# pj7.net
KiCad netlist of a schematic drawn in EAGLE
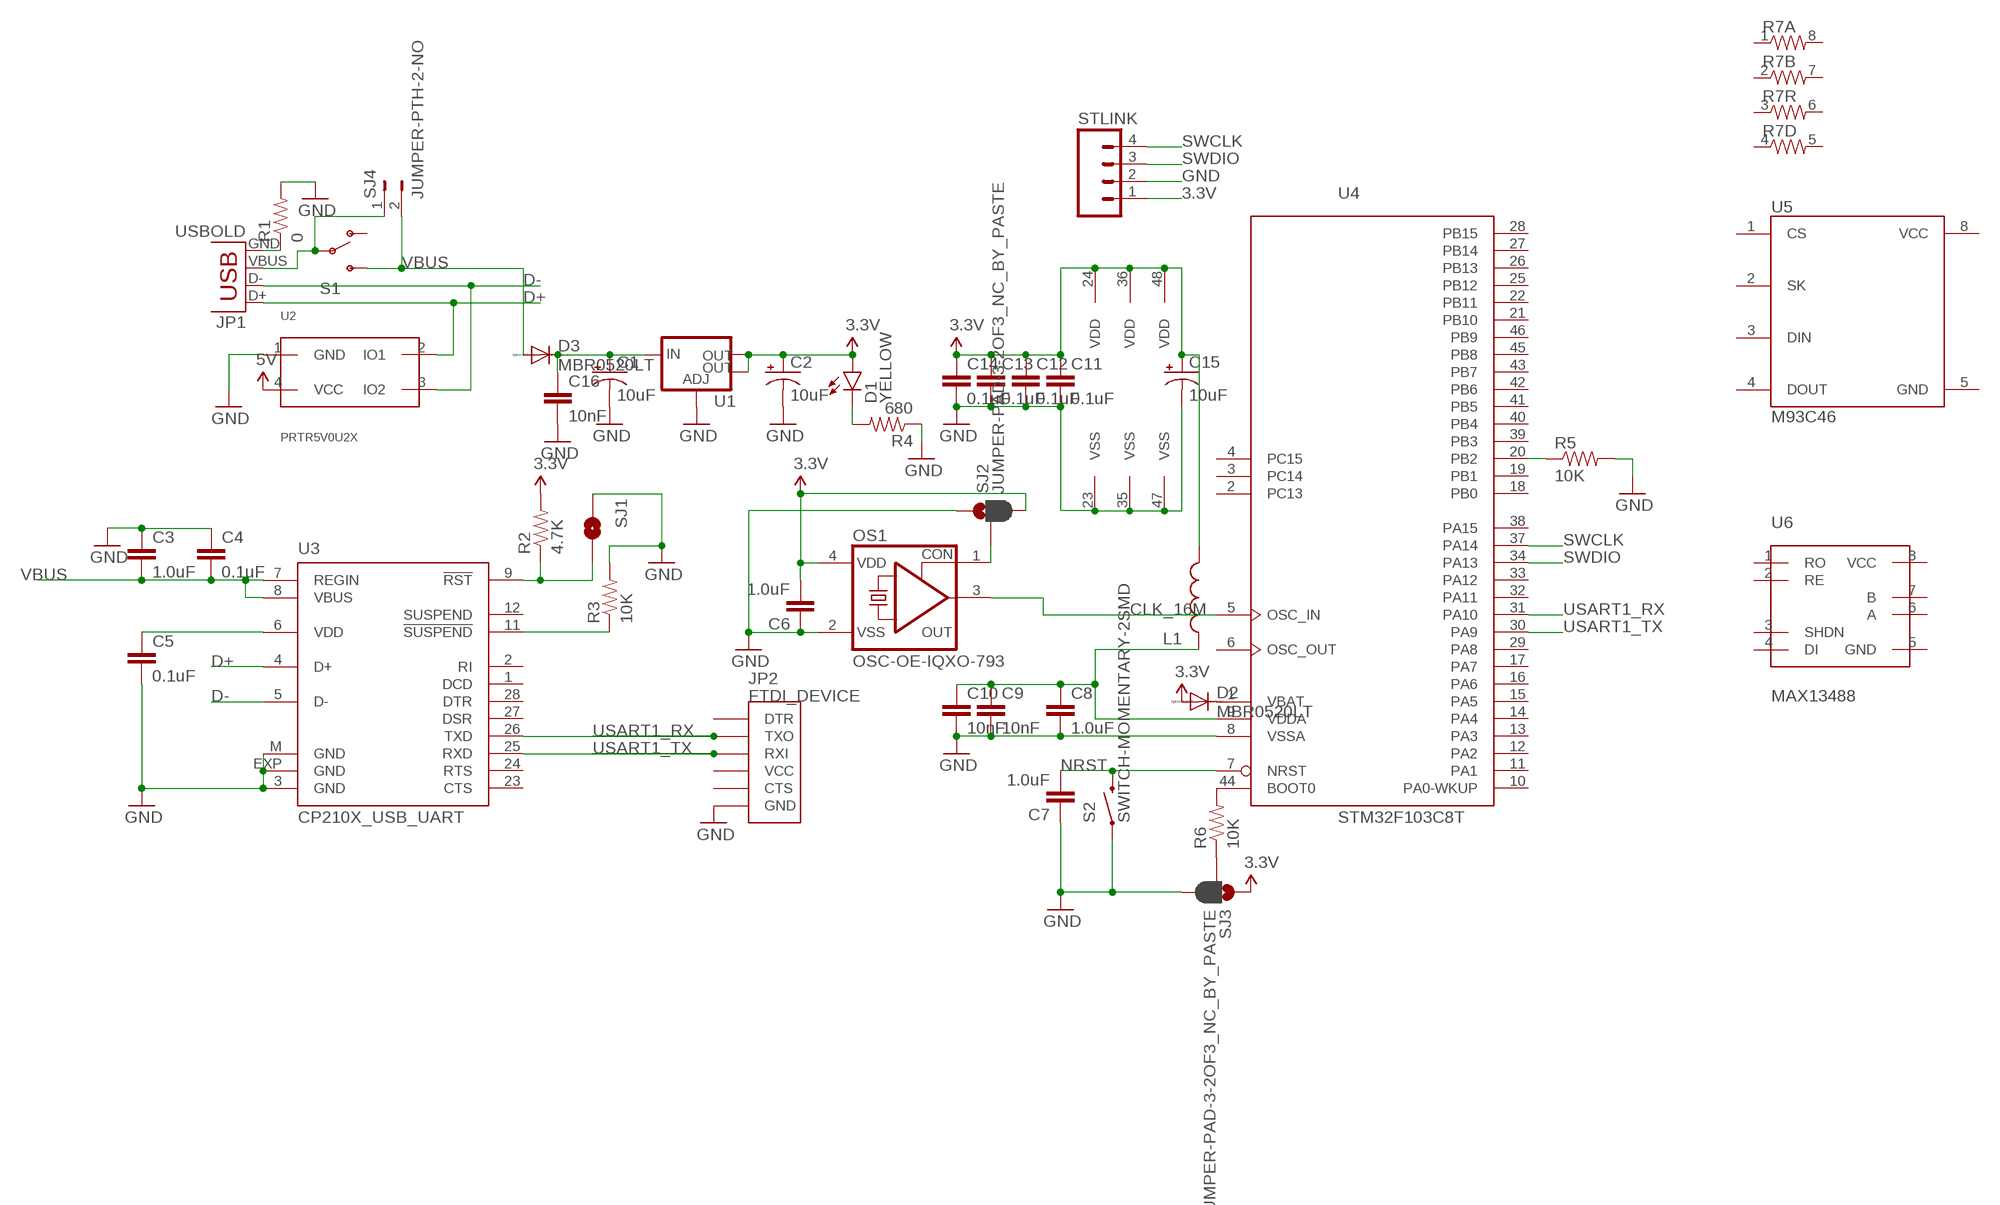
[diagram p0: schematic, sheet 1]

(export (version "E")
  (design (tool "Eeschema 10.0.6"))
  (components
    (comp (ref "C1")
      (value "10uF")
      (footprint "eagle-import:EIA3216")
      (libsource (lib "eagle-import") (part "10UF-16V-10%(TANT)"))
    )
    (comp (ref "C2")
      (value "10uF")
      (footprint "eagle-import:EIA3216")
      (libsource (lib "eagle-import") (part "10UF-16V-10%(TANT)"))
    )
    (comp (ref "C3")
      (value "1.0uF")
      (footprint "eagle-import:0603-CAP")
      (libsource (lib "eagle-import") (part "1.0UF-16V-10%(0603)"))
    )
    (comp (ref "C4")
      (value "0.1uF")
      (footprint "eagle-import:0603-CAP")
      (libsource (lib "eagle-import") (part "0.1UF-25V-5%(0603)"))
    )
    (comp (ref "C5")
      (value "0.1uF")
      (footprint "eagle-import:0603-CAP")
      (libsource (lib "eagle-import") (part "0.1UF-25V-5%(0603)"))
    )
    (comp (ref "C6")
      (value "1.0uF")
      (footprint "eagle-import:0603-CAP")
      (libsource (lib "eagle-import") (part "1.0UF-16V-10%(0603)"))
    )
    (comp (ref "C7")
      (value "1.0uF")
      (footprint "eagle-import:0603-CAP")
      (libsource (lib "eagle-import") (part "1.0UF-16V-10%(0603)"))
    )
    (comp (ref "C8")
      (value "1.0uF")
      (footprint "eagle-import:0603-CAP")
      (libsource (lib "eagle-import") (part "1.0UF-16V-10%(0603)"))
    )
    (comp (ref "C9")
      (value "10nF")
      (footprint "eagle-import:0603-CAP")
      (libsource (lib "eagle-import") (part "10NF/10000PF-50V-10%(0603)"))
    )
    (comp (ref "C10")
      (value "10nF")
      (footprint "eagle-import:0603-CAP")
      (libsource (lib "eagle-import") (part "10NF/10000PF-50V-10%(0603)"))
    )
    (comp (ref "C11")
      (value "0.1uF")
      (footprint "eagle-import:0603-CAP")
      (libsource (lib "eagle-import") (part "0.1UF-25V-5%(0603)"))
    )
    (comp (ref "C12")
      (value "0.1uF")
      (footprint "eagle-import:0603-CAP")
      (libsource (lib "eagle-import") (part "0.1UF-25V-5%(0603)"))
    )
    (comp (ref "C13")
      (value "0.1uF")
      (footprint "eagle-import:0603-CAP")
      (libsource (lib "eagle-import") (part "0.1UF-25V-5%(0603)"))
    )
    (comp (ref "C14")
      (value "0.1uF")
      (footprint "eagle-import:0603-CAP")
      (libsource (lib "eagle-import") (part "0.1UF-25V-5%(0603)"))
    )
    (comp (ref "C15")
      (value "10uF")
      (footprint "eagle-import:EIA3216")
      (libsource (lib "eagle-import") (part "10UF-16V-10%(TANT)"))
    )
    (comp (ref "C16")
      (value "10nF")
      (footprint "eagle-import:0603-CAP")
      (libsource (lib "eagle-import") (part "10NF/10000PF-50V-10%(0603)"))
    )
    (comp (ref "D1")
      (value "YELLOW")
      (footprint "eagle-import:LED-1206")
      (libsource (lib "eagle-import") (part "LED-YELLOW1206"))
    )
    (comp (ref "D2")
      (value "MBR0520LT")
      (footprint "eagle-import:SOD123")
      (libsource (lib "eagle-import") (part "MBR0520LT"))
    )
    (comp (ref "D3")
      (value "MBR0520LT")
      (footprint "eagle-import:SOD123")
      (libsource (lib "eagle-import") (part "MBR0520LT"))
    )
    (comp (ref "JP1")
      (value "USBOLD")
      (footprint "eagle-import:USB-MINIB-OLD")
      (libsource (lib "eagle-import") (part "USBOLD"))
    )
    (comp (ref "JP2")
      (value "FTDI_DEVICE")
      (footprint "eagle-import:FTDI_DEVICE_SIDE")
      (libsource (lib "eagle-import") (part "FTDI_DEVICE"))
    )
    (comp (ref "L1")
      (value "INDUCTOR0603")
      (footprint "eagle-import:0603")
      (libsource (lib "eagle-import") (part "INDUCTOR0603"))
    )
    (comp (ref "OS1")
      (value "OSC-OE-IQXO-793")
      (footprint "eagle-import:2.5X2-4-PAD")
      (libsource (lib "eagle-import") (part "OSC-OE-IQXO-793"))
    )
    (comp (ref "R1")
      (value "0")
      (footprint "eagle-import:0603")
      (libsource (lib "eagle-import") (part "0OHM-1/10W-5%(0603)"))
    )
    (comp (ref "R2")
      (value "4.7K")
      (footprint "eagle-import:0603-RES")
      (libsource (lib "eagle-import") (part "4.7KOHM-1/10W-1%(0603)"))
    )
    (comp (ref "R3")
      (value "10K")
      (footprint "eagle-import:0603-RES")
      (libsource (lib "eagle-import") (part "4.7KOHM-1/10W-1%(0603)"))
    )
    (comp (ref "R4")
      (value "680")
      (footprint "eagle-import:0603-RES")
      (libsource (lib "eagle-import") (part "680OHM1/10W5%(0603)"))
    )
    (comp (ref "R5")
      (value "10K")
      (footprint "eagle-import:0603-RES")
      (libsource (lib "eagle-import") (part "10KOHM-1/10W-1%(0603)0603"))
    )
    (comp (ref "R6")
      (value "10K")
      (footprint "eagle-import:0603-RES")
      (libsource (lib "eagle-import") (part "10KOHM-1/10W-1%(0603)0603"))
    )
    (comp (ref "R7")
      (value "RESISTOR-ARRAY0603-ARV")
      (footprint "eagle-import:0603-ARV")
      (libsource (lib "eagle-import") (part "RESISTOR-ARRAY0603-ARV"))
    )
    (comp (ref "S1")
      (value "SWITCH-SPDTSMD")
      (footprint "eagle-import:AYZ0202")
      (libsource (lib "eagle-import") (part "SWITCH-SPDTSMD"))
    )
    (comp (ref "S2")
      (value "SWITCH-MOMENTARY-2SMD")
      (footprint "eagle-import:TACTILE-SWITCH-SMD")
      (libsource (lib "eagle-import") (part "SWITCH-MOMENTARY-2SMD"))
    )
    (comp (ref "SJ1")
      (value "JUMPER-PAD-2-NOYES_SILK")
      (footprint "eagle-import:PAD-JUMPER-2-NO_YES_SILK")
      (libsource (lib "eagle-import") (part "JUMPER-PAD-2-NOYES_SILK"))
    )
    (comp (ref "SJ2")
      (value "JUMPER-PAD-3-2OF3_NC_BY_PASTE")
      (footprint "eagle-import:PAD-JUMPER-3-2OF3_NC_BY_PASTE_YES_SILK_FULL_BOX")
      (libsource (lib "eagle-import") (part "JUMPER-PAD-3-2OF3_NC_BY_PASTE"))
    )
    (comp (ref "SJ3")
      (value "JUMPER-PAD-3-2OF3_NC_BY_PASTE")
      (footprint "eagle-import:PAD-JUMPER-3-2OF3_NC_BY_PASTE_YES_SILK_FULL_BOX")
      (libsource (lib "eagle-import") (part "JUMPER-PAD-3-2OF3_NC_BY_PASTE"))
    )
    (comp (ref "SJ4")
      (value "JUMPER-PTH-2-NO")
      (footprint "eagle-import:PTH-JUMPER-2-NO_NO_SILK")
      (libsource (lib "eagle-import") (part "JUMPER-PTH-2-NO"))
    )
    (comp (ref "STLINK")
      (value "M04LOCK")
      (footprint "eagle-import:1X04_LOCK")
      (libsource (lib "eagle-import") (part "M04LOCK"))
    )
    (comp (ref "U1")
      (value "V_REG_LM1117SOT223")
      (footprint "eagle-import:SOT223")
      (libsource (lib "eagle-import") (part "V_REG_LM1117SOT223"))
    )
    (comp (ref "U2")
      (value "PRTR5V0U2X")
      (footprint "eagle-import:SOT143")
      (libsource (lib "eagle-import") (part "PRTR5V0U2X"))
    )
    (comp (ref "U3")
      (value "CP210X_USB_UART")
      (footprint "eagle-import:MLP28")
      (libsource (lib "eagle-import") (part "CP210X_USB_UART"))
    )
    (comp (ref "U4")
      (value "STM32F103C8T")
      (footprint "eagle-import:LQFP48")
      (libsource (lib "eagle-import") (part "STM32F103CT8"))
    )
    (comp (ref "U5")
      (value "M93C46")
      (footprint "eagle-import:SO08")
      (libsource (lib "eagle-import") (part "M93C46"))
    )
    (comp (ref "U6")
      (value "MAX13488")
      (footprint "eagle-import:SOIC8")
      (libsource (lib "eagle-import") (part "MAX13488"))
    )
  )
  (nets
    (net (code "1") (name "/CLK_16M") (class "Default")
      (node (ref "OS1") (pin "3") (pinfunction "OUT_3") (pintype "output"))
      (node (ref "U4") (pin "5") (pinfunction "OSC_IN_5") (pintype "bidirectional"))
    )
    (net (code "2") (name "/D+") (class "Default")
      (node (ref "JP1") (pin "D+") (pinfunction "D+_D+") (pintype "bidirectional"))
      (node (ref "U2") (pin "2") (pinfunction "IO1_2") (pintype "bidirectional"))
      (node (ref "U3") (pin "4") (pinfunction "D+_4") (pintype "bidirectional"))
    )
    (net (code "3") (name "/D-") (class "Default")
      (node (ref "JP1") (pin "D-") (pinfunction "D-_D-") (pintype "bidirectional"))
      (node (ref "U2") (pin "3") (pinfunction "IO2_3") (pintype "bidirectional"))
      (node (ref "U3") (pin "5") (pinfunction "D-_5") (pintype "bidirectional"))
    )
    (net (code "4") (name "/NRST") (class "Default")
      (node (ref "C7") (pin "2") (pinfunction "2_2") (pintype "passive"))
      (node (ref "S2") (pin "3") (pinfunction "2_3") (pintype "passive"))
      (node (ref "U4") (pin "7") (pinfunction "NRST_7") (pintype "bidirectional"))
    )
    (net (code "5") (name "/SWCLK") (class "Default")
      (node (ref "STLINK") (pin "4") (pinfunction "4_4") (pintype "passive"))
      (node (ref "U4") (pin "37") (pinfunction "PA14_37") (pintype "bidirectional"))
    )
    (net (code "6") (name "/SWDIO") (class "Default")
      (node (ref "STLINK") (pin "3") (pinfunction "3_3") (pintype "passive"))
      (node (ref "U4") (pin "34") (pinfunction "PA13_34") (pintype "bidirectional"))
    )
    (net (code "7") (name "/USART1_RX") (class "Default")
      (node (ref "JP2") (pin "P$2") (pinfunction "TXO_P$2") (pintype "bidirectional"))
      (node (ref "U3") (pin "26") (pinfunction "TXD_26") (pintype "output"))
      (node (ref "U4") (pin "31") (pinfunction "PA10_31") (pintype "bidirectional"))
    )
    (net (code "8") (name "/USART1_TX") (class "Default")
      (node (ref "JP2") (pin "P$3") (pinfunction "RXI_P$3") (pintype "bidirectional"))
      (node (ref "U3") (pin "25") (pinfunction "RXD_25") (pintype "input"))
      (node (ref "U4") (pin "30") (pinfunction "PA9_30") (pintype "bidirectional"))
    )
    (net (code "9") (name "/VBUS") (class "Default")
      (node (ref "C3") (pin "2") (pinfunction "2_2") (pintype "passive"))
      (node (ref "C4") (pin "2") (pinfunction "2_2") (pintype "passive"))
      (node (ref "D3") (pin "A") (pinfunction "A_A") (pintype "passive"))
      (node (ref "S1") (pin "3") (pinfunction "S_3") (pintype "passive"))
      (node (ref "SJ4") (pin "2") (pinfunction "2_2") (pintype "passive"))
      (node (ref "U3") (pin "7") (pinfunction "REGIN_7") (pintype "passive"))
      (node (ref "U3") (pin "8") (pinfunction "VBUS_8") (pintype "input"))
    )
    (net (code "10") (name "3.3V") (class "Default")
      (node (ref "C11") (pin "1") (pinfunction "1_1") (pintype "passive"))
      (node (ref "C12") (pin "1") (pinfunction "1_1") (pintype "passive"))
      (node (ref "C13") (pin "1") (pinfunction "1_1") (pintype "passive"))
      (node (ref "C14") (pin "1") (pinfunction "1_1") (pintype "passive"))
      (node (ref "C15") (pin "A") (pinfunction "+_A") (pintype "passive"))
      (node (ref "C2") (pin "A") (pinfunction "+_A") (pintype "passive"))
      (node (ref "C6") (pin "2") (pinfunction "2_2") (pintype "passive"))
      (node (ref "D1") (pin "A") (pinfunction "A_A") (pintype "passive"))
      (node (ref "D2") (pin "A") (pinfunction "A_A") (pintype "passive"))
      (node (ref "L1") (pin "2") (pinfunction "2_2") (pintype "passive"))
      (node (ref "OS1") (pin "4") (pinfunction "VDD_4") (pintype "power_in"))
      (node (ref "R2") (pin "2") (pinfunction "2_2") (pintype "passive"))
      (node (ref "SJ2") (pin "3") (pinfunction "3_3") (pintype "passive"))
      (node (ref "SJ3") (pin "1") (pinfunction "1_1") (pintype "passive"))
      (node (ref "STLINK") (pin "1") (pinfunction "1_1") (pintype "passive"))
      (node (ref "U1") (pin "2") (pinfunction "OUT_2") (pintype "output"))
      (node (ref "U1") (pin "4") (pinfunction "OUT_4") (pintype "output"))
      (node (ref "U4") (pin "24") (pinfunction "VDD_24") (pintype "power_in"))
      (node (ref "U4") (pin "36") (pinfunction "VDD_36") (pintype "power_in"))
      (node (ref "U4") (pin "48") (pinfunction "VDD_48") (pintype "power_in"))
    )
    (net (code "11") (name "5V") (class "Default")
      (node (ref "U2") (pin "4") (pinfunction "VCC_4") (pintype "bidirectional"))
    )
    (net (code "12") (name "GND") (class "Default")
      (node (ref "C1") (pin "C") (pinfunction "-_C") (pintype "passive"))
      (node (ref "C10") (pin "2") (pinfunction "2_2") (pintype "passive"))
      (node (ref "C11") (pin "2") (pinfunction "2_2") (pintype "passive"))
      (node (ref "C12") (pin "2") (pinfunction "2_2") (pintype "passive"))
      (node (ref "C13") (pin "2") (pinfunction "2_2") (pintype "passive"))
      (node (ref "C14") (pin "2") (pinfunction "2_2") (pintype "passive"))
      (node (ref "C15") (pin "C") (pinfunction "-_C") (pintype "passive"))
      (node (ref "C16") (pin "2") (pinfunction "2_2") (pintype "passive"))
      (node (ref "C2") (pin "C") (pinfunction "-_C") (pintype "passive"))
      (node (ref "C3") (pin "1") (pinfunction "1_1") (pintype "passive"))
      (node (ref "C4") (pin "1") (pinfunction "1_1") (pintype "passive"))
      (node (ref "C5") (pin "2") (pinfunction "2_2") (pintype "passive"))
      (node (ref "C6") (pin "1") (pinfunction "1_1") (pintype "passive"))
      (node (ref "C7") (pin "1") (pinfunction "1_1") (pintype "passive"))
      (node (ref "C8") (pin "2") (pinfunction "2_2") (pintype "passive"))
      (node (ref "C9") (pin "2") (pinfunction "2_2") (pintype "passive"))
      (node (ref "JP2") (pin "P$6") (pinfunction "GND_P$6") (pintype "bidirectional"))
      (node (ref "OS1") (pin "2") (pinfunction "VSS_2") (pintype "power_in"))
      (node (ref "R1") (pin "2") (pinfunction "2_2") (pintype "passive"))
      (node (ref "R3") (pin "2") (pinfunction "2_2") (pintype "passive"))
      (node (ref "R4") (pin "1") (pinfunction "1_1") (pintype "passive"))
      (node (ref "R5") (pin "2") (pinfunction "2_2") (pintype "passive"))
      (node (ref "S2") (pin "1") (pinfunction "1_1") (pintype "passive"))
      (node (ref "SJ1") (pin "2") (pinfunction "2_2") (pintype "passive"))
      (node (ref "SJ2") (pin "1") (pinfunction "1_1") (pintype "passive"))
      (node (ref "SJ3") (pin "3") (pinfunction "3_3") (pintype "passive"))
      (node (ref "STLINK") (pin "2") (pinfunction "2_2") (pintype "passive"))
      (node (ref "U1") (pin "1") (pinfunction "ADJ_1") (pintype "input"))
      (node (ref "U2") (pin "1") (pinfunction "GND_1") (pintype "bidirectional"))
      (node (ref "U3") (pin "3") (pinfunction "GND_3") (pintype "power_in"))
      (node (ref "U3") (pin "EXP") (pinfunction "GND_EXP") (pintype "power_in"))
      (node (ref "U3") (pin "M") (pinfunction "GND_M") (pintype "power_in"))
      (node (ref "U4") (pin "23") (pinfunction "VSS_23") (pintype "power_in"))
      (node (ref "U4") (pin "35") (pinfunction "VSS_35") (pintype "power_in"))
      (node (ref "U4") (pin "47") (pinfunction "VSS_47") (pintype "power_in"))
      (node (ref "U4") (pin "8") (pinfunction "VSSA_8") (pintype "power_in"))
    )
    (net (code "13") (name "Net-(C1-+)") (class "Default")
      (node (ref "C1") (pin "A") (pinfunction "+_A") (pintype "passive"))
      (node (ref "C16") (pin "1") (pinfunction "1_1") (pintype "passive"))
      (node (ref "D3") (pin "C") (pinfunction "C_C") (pintype "passive"))
      (node (ref "U1") (pin "3") (pinfunction "IN_3") (pintype "input"))
    )
    (net (code "14") (name "Net-(D1-PadC)") (class "Default")
      (node (ref "D1") (pin "C") (pinfunction "C_C") (pintype "passive"))
      (node (ref "R4") (pin "2") (pinfunction "2_2") (pintype "passive"))
    )
    (net (code "15") (name "Net-(JP1-PadGND)") (class "Default")
      (node (ref "JP1") (pin "GND") (pinfunction "GND_GND") (pintype "bidirectional"))
      (node (ref "R1") (pin "1") (pinfunction "1_1") (pintype "passive"))
    )
    (net (code "16") (name "Net-(OS1-CON)") (class "Default")
      (node (ref "OS1") (pin "1") (pinfunction "CON_1") (pintype "input"))
      (node (ref "SJ2") (pin "2") (pinfunction "2_2") (pintype "passive"))
    )
    (net (code "17") (name "Net-(R6-Pad1)") (class "Default")
      (node (ref "R6") (pin "1") (pinfunction "1_1") (pintype "passive"))
      (node (ref "SJ3") (pin "2") (pinfunction "2_2") (pintype "passive"))
    )
    (net (code "18") (name "Net-(S1-P)") (class "Default")
      (node (ref "JP1") (pin "VBUS") (pinfunction "VBUS_VBUS") (pintype "bidirectional"))
      (node (ref "S1") (pin "2") (pinfunction "P_2") (pintype "passive"))
      (node (ref "SJ4") (pin "1") (pinfunction "1_1") (pintype "passive"))
    )
    (net (code "19") (name "Net-(U3-VDD)") (class "Default")
      (node (ref "C5") (pin "1") (pinfunction "1_1") (pintype "passive"))
      (node (ref "U3") (pin "6") (pinfunction "VDD_6") (pintype "power_in"))
    )
    (net (code "20") (name "Net-(U3-~{RST})") (class "Default")
      (node (ref "R2") (pin "1") (pinfunction "1_1") (pintype "passive"))
      (node (ref "SJ1") (pin "1") (pinfunction "1_1") (pintype "passive"))
      (node (ref "U3") (pin "9") (pinfunction "~{RST}_9") (pintype "bidirectional"))
    )
    (net (code "21") (name "Net-(U3-~{SUSPEND})") (class "Default")
      (node (ref "R3") (pin "1") (pinfunction "1_1") (pintype "passive"))
      (node (ref "U3") (pin "11") (pinfunction "~{SUSPEND}_11") (pintype "output"))
    )
    (net (code "22") (name "Net-(U4A-BOOT0)") (class "Default")
      (node (ref "R6") (pin "2") (pinfunction "2_2") (pintype "passive"))
      (node (ref "U4") (pin "44") (pinfunction "BOOT0_44") (pintype "input"))
    )
    (net (code "23") (name "Net-(U4A-PB2)") (class "Default")
      (node (ref "R5") (pin "1") (pinfunction "1_1") (pintype "passive"))
      (node (ref "U4") (pin "20") (pinfunction "PB2_20") (pintype "bidirectional"))
    )
    (net (code "24") (name "Net-(U4A-VBAT)") (class "Default")
      (node (ref "D2") (pin "C") (pinfunction "C_C") (pintype "passive"))
      (node (ref "U4") (pin "1") (pinfunction "VBAT_1") (pintype "power_in"))
    )
    (net (code "25") (name "Net-(U4A-VDDA)") (class "Default")
      (node (ref "C10") (pin "1") (pinfunction "1_1") (pintype "passive"))
      (node (ref "C8") (pin "1") (pinfunction "1_1") (pintype "passive"))
      (node (ref "C9") (pin "1") (pinfunction "1_1") (pintype "passive"))
      (node (ref "L1") (pin "1") (pinfunction "1_1") (pintype "passive"))
      (node (ref "U4") (pin "9") (pinfunction "VDDA_9") (pintype "power_in"))
    )
    (net (code "26") (name "unconnected-(JP2-CTS-PadP$5)") (class "Default")
      (node (ref "JP2") (pin "P$5") (pinfunction "CTS_P$5") (pintype "bidirectional"))
    )
    (net (code "27") (name "unconnected-(JP2-DTR-PadP$1)") (class "Default")
      (node (ref "JP2") (pin "P$1") (pinfunction "DTR_P$1") (pintype "bidirectional"))
    )
    (net (code "28") (name "unconnected-(JP2-VCC-PadP$4)") (class "Default")
      (node (ref "JP2") (pin "P$4") (pinfunction "VCC_P$4") (pintype "bidirectional"))
    )
    (net (code "29") (name "unconnected-(R7-Pad1)") (class "Default")
      (node (ref "R7") (pin "1") (pinfunction "1_1") (pintype "passive"))
    )
    (net (code "30") (name "unconnected-(R7A-2-Pad8)") (class "Default")
      (node (ref "R7") (pin "8") (pinfunction "2_8") (pintype "passive"))
    )
    (net (code "31") (name "unconnected-(R7B-1-Pad2)") (class "Default")
      (node (ref "R7") (pin "2") (pinfunction "1_2") (pintype "passive"))
    )
    (net (code "32") (name "unconnected-(R7B-2-Pad7)") (class "Default")
      (node (ref "R7") (pin "7") (pinfunction "2_7") (pintype "passive"))
    )
    (net (code "33") (name "unconnected-(R7C-1-Pad4)") (class "Default")
      (node (ref "R7") (pin "4") (pinfunction "1_4") (pintype "passive"))
    )
    (net (code "34") (name "unconnected-(R7C-2-Pad5)") (class "Default")
      (node (ref "R7") (pin "5") (pinfunction "2_5") (pintype "passive"))
    )
    (net (code "35") (name "unconnected-(R7D-1-Pad3)") (class "Default")
      (node (ref "R7") (pin "3") (pinfunction "1_3") (pintype "passive"))
    )
    (net (code "36") (name "unconnected-(R7D-2-Pad6)") (class "Default")
      (node (ref "R7") (pin "6") (pinfunction "2_6") (pintype "passive"))
    )
    (net (code "37") (name "unconnected-(S1-O-Pad1)") (class "Default")
      (node (ref "S1") (pin "1") (pinfunction "O_1") (pintype "passive"))
    )
    (net (code "38") (name "unconnected-(U3-CTS-Pad23)") (class "Default")
      (node (ref "U3") (pin "23") (pinfunction "CTS_23") (pintype "input"))
    )
    (net (code "39") (name "unconnected-(U3-DCD-Pad1)") (class "Default")
      (node (ref "U3") (pin "1") (pinfunction "DCD_1") (pintype "input"))
    )
    (net (code "40") (name "unconnected-(U3-DSR-Pad27)") (class "Default")
      (node (ref "U3") (pin "27") (pinfunction "DSR_27") (pintype "input"))
    )
    (net (code "41") (name "unconnected-(U3-DTR-Pad28)") (class "Default")
      (node (ref "U3") (pin "28") (pinfunction "DTR_28") (pintype "output"))
    )
    (net (code "42") (name "unconnected-(U3-RI-Pad2)") (class "Default")
      (node (ref "U3") (pin "2") (pinfunction "RI_2") (pintype "input"))
    )
    (net (code "43") (name "unconnected-(U3-RTS-Pad24)") (class "Default")
      (node (ref "U3") (pin "24") (pinfunction "RTS_24") (pintype "output"))
    )
    (net (code "44") (name "unconnected-(U3-SUSPEND-Pad12)") (class "Default")
      (node (ref "U3") (pin "12") (pinfunction "SUSPEND_12") (pintype "output"))
    )
    (net (code "45") (name "unconnected-(U4A-OSC_OUT-Pad6)") (class "Default")
      (node (ref "U4") (pin "6") (pinfunction "OSC_OUT_6") (pintype "bidirectional"))
    )
    (net (code "46") (name "unconnected-(U4A-PA0-WKUP-Pad10)") (class "Default")
      (node (ref "U4") (pin "10") (pinfunction "PA0-WKUP_10") (pintype "bidirectional"))
    )
    (net (code "47") (name "unconnected-(U4A-PA1-Pad11)") (class "Default")
      (node (ref "U4") (pin "11") (pinfunction "PA1_11") (pintype "bidirectional"))
    )
    (net (code "48") (name "unconnected-(U4A-PA2-Pad12)") (class "Default")
      (node (ref "U4") (pin "12") (pinfunction "PA2_12") (pintype "bidirectional"))
    )
    (net (code "49") (name "unconnected-(U4A-PA3-Pad13)") (class "Default")
      (node (ref "U4") (pin "13") (pinfunction "PA3_13") (pintype "bidirectional"))
    )
    (net (code "50") (name "unconnected-(U4A-PA4-Pad14)") (class "Default")
      (node (ref "U4") (pin "14") (pinfunction "PA4_14") (pintype "bidirectional"))
    )
    (net (code "51") (name "unconnected-(U4A-PA5-Pad15)") (class "Default")
      (node (ref "U4") (pin "15") (pinfunction "PA5_15") (pintype "bidirectional"))
    )
    (net (code "52") (name "unconnected-(U4A-PA6-Pad16)") (class "Default")
      (node (ref "U4") (pin "16") (pinfunction "PA6_16") (pintype "bidirectional"))
    )
    (net (code "53") (name "unconnected-(U4A-PA7-Pad17)") (class "Default")
      (node (ref "U4") (pin "17") (pinfunction "PA7_17") (pintype "bidirectional"))
    )
    (net (code "54") (name "unconnected-(U4A-PA8-Pad29)") (class "Default")
      (node (ref "U4") (pin "29") (pinfunction "PA8_29") (pintype "bidirectional"))
    )
    (net (code "55") (name "unconnected-(U4A-PA11-Pad32)") (class "Default")
      (node (ref "U4") (pin "32") (pinfunction "PA11_32") (pintype "bidirectional"))
    )
    (net (code "56") (name "unconnected-(U4A-PA12-Pad33)") (class "Default")
      (node (ref "U4") (pin "33") (pinfunction "PA12_33") (pintype "bidirectional"))
    )
    (net (code "57") (name "unconnected-(U4A-PA15-Pad38)") (class "Default")
      (node (ref "U4") (pin "38") (pinfunction "PA15_38") (pintype "bidirectional"))
    )
    (net (code "58") (name "unconnected-(U4A-PB0-Pad18)") (class "Default")
      (node (ref "U4") (pin "18") (pinfunction "PB0_18") (pintype "bidirectional"))
    )
    (net (code "59") (name "unconnected-(U4A-PB1-Pad19)") (class "Default")
      (node (ref "U4") (pin "19") (pinfunction "PB1_19") (pintype "bidirectional"))
    )
    (net (code "60") (name "unconnected-(U4A-PB3-Pad39)") (class "Default")
      (node (ref "U4") (pin "39") (pinfunction "PB3_39") (pintype "bidirectional"))
    )
    (net (code "61") (name "unconnected-(U4A-PB4-Pad40)") (class "Default")
      (node (ref "U4") (pin "40") (pinfunction "PB4_40") (pintype "bidirectional"))
    )
    (net (code "62") (name "unconnected-(U4A-PB5-Pad41)") (class "Default")
      (node (ref "U4") (pin "41") (pinfunction "PB5_41") (pintype "bidirectional"))
    )
    (net (code "63") (name "unconnected-(U4A-PB6-Pad42)") (class "Default")
      (node (ref "U4") (pin "42") (pinfunction "PB6_42") (pintype "bidirectional"))
    )
    (net (code "64") (name "unconnected-(U4A-PB7-Pad43)") (class "Default")
      (node (ref "U4") (pin "43") (pinfunction "PB7_43") (pintype "bidirectional"))
    )
    (net (code "65") (name "unconnected-(U4A-PB8-Pad45)") (class "Default")
      (node (ref "U4") (pin "45") (pinfunction "PB8_45") (pintype "bidirectional"))
    )
    (net (code "66") (name "unconnected-(U4A-PB9-Pad46)") (class "Default")
      (node (ref "U4") (pin "46") (pinfunction "PB9_46") (pintype "bidirectional"))
    )
    (net (code "67") (name "unconnected-(U4A-PB10-Pad21)") (class "Default")
      (node (ref "U4") (pin "21") (pinfunction "PB10_21") (pintype "bidirectional"))
    )
    (net (code "68") (name "unconnected-(U4A-PB11-Pad22)") (class "Default")
      (node (ref "U4") (pin "22") (pinfunction "PB11_22") (pintype "bidirectional"))
    )
    (net (code "69") (name "unconnected-(U4A-PB12-Pad25)") (class "Default")
      (node (ref "U4") (pin "25") (pinfunction "PB12_25") (pintype "bidirectional"))
    )
    (net (code "70") (name "unconnected-(U4A-PB13-Pad26)") (class "Default")
      (node (ref "U4") (pin "26") (pinfunction "PB13_26") (pintype "bidirectional"))
    )
    (net (code "71") (name "unconnected-(U4A-PB14-Pad27)") (class "Default")
      (node (ref "U4") (pin "27") (pinfunction "PB14_27") (pintype "bidirectional"))
    )
    (net (code "72") (name "unconnected-(U4A-PB15-Pad28)") (class "Default")
      (node (ref "U4") (pin "28") (pinfunction "PB15_28") (pintype "bidirectional"))
    )
    (net (code "73") (name "unconnected-(U4A-PC13-Pad2)") (class "Default")
      (node (ref "U4") (pin "2") (pinfunction "PC13_2") (pintype "bidirectional"))
    )
    (net (code "74") (name "unconnected-(U4A-PC14-Pad3)") (class "Default")
      (node (ref "U4") (pin "3") (pinfunction "PC14_3") (pintype "bidirectional"))
    )
    (net (code "75") (name "unconnected-(U4A-PC15-Pad4)") (class "Default")
      (node (ref "U4") (pin "4") (pinfunction "PC15_4") (pintype "bidirectional"))
    )
    (net (code "76") (name "unconnected-(U5-CS-Pad1)") (class "Default")
      (node (ref "U5") (pin "1") (pinfunction "CS_1") (pintype "bidirectional"))
    )
    (net (code "77") (name "unconnected-(U5-DIN-Pad3)") (class "Default")
      (node (ref "U5") (pin "3") (pinfunction "DIN_3") (pintype "bidirectional"))
    )
    (net (code "78") (name "unconnected-(U5-DOUT-Pad4)") (class "Default")
      (node (ref "U5") (pin "4") (pinfunction "DOUT_4") (pintype "bidirectional"))
    )
    (net (code "79") (name "unconnected-(U5-GND-Pad5)") (class "Default")
      (node (ref "U5") (pin "5") (pinfunction "GND_5") (pintype "bidirectional"))
    )
    (net (code "80") (name "unconnected-(U5-SK-Pad2)") (class "Default")
      (node (ref "U5") (pin "2") (pinfunction "SK_2") (pintype "bidirectional"))
    )
    (net (code "81") (name "unconnected-(U5-VCC-Pad8)") (class "Default")
      (node (ref "U5") (pin "8") (pinfunction "VCC_8") (pintype "bidirectional"))
    )
    (net (code "82") (name "unconnected-(U6-A-Pad6)") (class "Default")
      (node (ref "U6") (pin "6") (pinfunction "A_6") (pintype "bidirectional"))
    )
    (net (code "83") (name "unconnected-(U6-B-Pad7)") (class "Default")
      (node (ref "U6") (pin "7") (pinfunction "B_7") (pintype "bidirectional"))
    )
    (net (code "84") (name "unconnected-(U6-DI-Pad4)") (class "Default")
      (node (ref "U6") (pin "4") (pinfunction "DI_4") (pintype "bidirectional"))
    )
    (net (code "85") (name "unconnected-(U6-GND-Pad5)") (class "Default")
      (node (ref "U6") (pin "5") (pinfunction "GND_5") (pintype "bidirectional"))
    )
    (net (code "86") (name "unconnected-(U6-RE-Pad2)") (class "Default")
      (node (ref "U6") (pin "2") (pinfunction "RE_2") (pintype "bidirectional"))
    )
    (net (code "87") (name "unconnected-(U6-RO-Pad1)") (class "Default")
      (node (ref "U6") (pin "1") (pinfunction "RO_1") (pintype "bidirectional"))
    )
    (net (code "88") (name "unconnected-(U6-SHDN-Pad3)") (class "Default")
      (node (ref "U6") (pin "3") (pinfunction "SHDN_3") (pintype "bidirectional"))
    )
    (net (code "89") (name "unconnected-(U6-VCC-Pad8)") (class "Default")
      (node (ref "U6") (pin "8") (pinfunction "VCC_8") (pintype "bidirectional"))
    )
  )
)
